# drive.net
KiCad netlist of a schematic drawn in Altium Designer
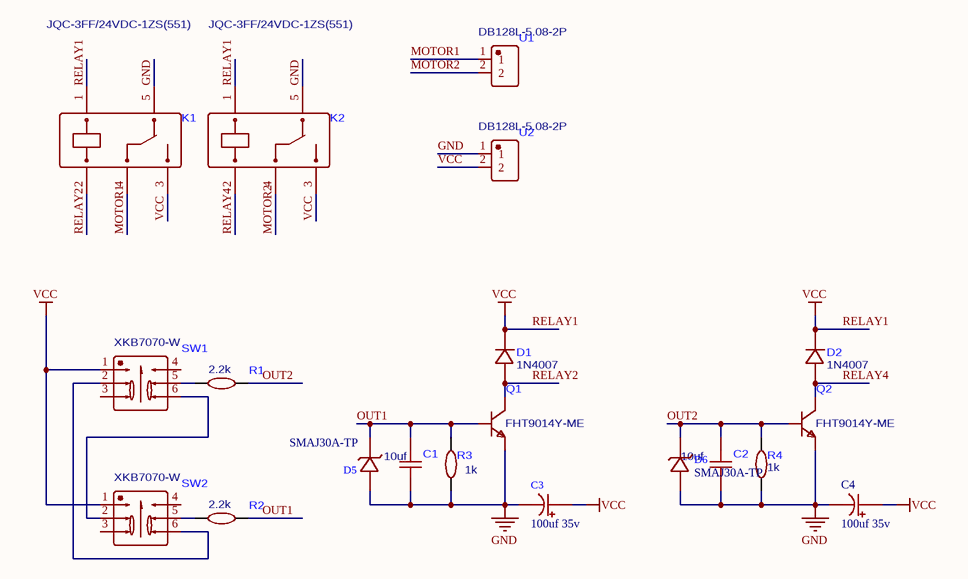
[diagram p0: drive.SchDoc]

(export (version "E")
  (design (tool "Eeschema 10.0.6"))
  (components
    (comp (ref "C1") (value "10uf") (footprint "C1210") (libsource (lib "test") (part "EMK325ABJ107MM-P")))
    (comp (ref "C2") (value "10uf") (footprint "C1210") (libsource (lib "test") (part "EMK325ABJ107MM-P")))
    (comp (ref "C3") (value "100uf 35v") (footprint "100uf 35v") (libsource (lib "test") (part "100uf 35v")))
    (comp (ref "C4") (value "100uf 35v") (footprint "100uf 35v") (libsource (lib "test") (part "100uf 35v")))
    (comp (ref "D1")
      (value "1N4007")
      (footprint "SMA_L4.4-W2.6-LS5.0-RD")
      (libsource (lib "test") (part "1N4007"))
    )
    (comp (ref "D2")
      (value "1N4007")
      (footprint "SMA_L4.4-W2.6-LS5.0-RD")
      (libsource (lib "test") (part "1N4007"))
    )
    (comp (ref "D5")
      (value "SMAJ30A-TP")
      (footprint "SMAJ16A-TP")
      (libsource (lib "test") (part "SMAJ16A-TP"))
    )
    (comp (ref "D6")
      (value "SMAJ30A-TP")
      (footprint "SMAJ16A-TP")
      (libsource (lib "test") (part "SMAJ16A-TP"))
    )
    (comp (ref "K1")
      (value "JQC-3FF/24VDC-1ZS(551)")
      (footprint "RELAY-TH_HF3FF/XX-1ZXX(XXX)")
      (libsource (lib "test") (part "JQC-3FF/12VDC-1ZS(551)"))
    )
    (comp (ref "K2")
      (value "JQC-3FF/24VDC-1ZS(551)")
      (footprint "RELAY-TH_HF3FF/XX-1ZXX(XXX)")
      (libsource (lib "test") (part "JQC-3FF/12VDC-1ZS(551)"))
    )
    (comp (ref "Q1")
      (value "FHT9014Y-ME")
      (footprint "SOT-23-3_L2.9-W1.3-P1.90-LS2.4-BR")
      (libsource (lib "test") (part "FHT9014Y-ME"))
    )
    (comp (ref "Q2")
      (value "FHT9014Y-ME")
      (footprint "SOT-23-3_L2.9-W1.3-P1.90-LS2.4-BR")
      (libsource (lib "test") (part "FHT9014Y-ME"))
    )
    (comp (ref "R1") (value "2.2k") (footprint "R0402") (libsource (lib "test") (part "MFR0S2F1001A20")))
    (comp (ref "R2") (value "2.2k") (footprint "R0402") (libsource (lib "test") (part "MFR0S2F1001A20")))
    (comp (ref "R3") (value "1k") (footprint "R0402") (libsource (lib "test") (part "MFR0S2F1001A20")))
    (comp (ref "R4") (value "1k") (footprint "R0402") (libsource (lib "test") (part "MFR0S2F1001A20")))
    (comp (ref "SW1")
      (value "XKB7070-W")
      (footprint "SW-TH_6P-L7.2-W7.2-P2.00-LS5.0")
      (libsource (lib "test") (part "XKB7070-W"))
    )
    (comp (ref "SW2")
      (value "XKB7070-W")
      (footprint "SW-TH_6P-L7.2-W7.2-P2.00-LS5.0")
      (libsource (lib "test") (part "XKB7070-W"))
    )
    (comp (ref "U1")
      (value "DB128L-5.08-2P")
      (footprint "CONN-TH_2P-P5.08_DB128L-5.08-2P")
      (libsource (lib "test") (part "DB128L-5.08-2P"))
    )
    (comp (ref "U2")
      (value "DB128L-5.08-2P")
      (footprint "CONN-TH_2P-P5.08_DB128L-5.08-2P")
      (libsource (lib "test") (part "DB128L-5.08-2P"))
    )
  )
  (nets
    (net (code "1") (name "/MOTOR1") (class "Default")
      (node (ref "K1") (pin "4") (pinfunction "4_4") (pintype "passive"))
      (node (ref "U1") (pin "1") (pinfunction "1_1") (pintype "passive"))
    )
    (net (code "2") (name "/MOTOR2") (class "Default")
      (node (ref "K2") (pin "4") (pinfunction "4_4") (pintype "passive"))
      (node (ref "U1") (pin "2") (pinfunction "2_2") (pintype "passive"))
    )
    (net (code "3") (name "/OUT1") (class "Default")
      (node (ref "C1") (pin "1") (pinfunction "1_1") (pintype "passive"))
      (node (ref "D5") (pin "1") (pinfunction "K_1") (pintype "passive"))
      (node (ref "Q1") (pin "1") (pinfunction "B_1") (pintype "passive"))
      (node (ref "R2") (pin "2") (pinfunction "2_2") (pintype "passive"))
      (node (ref "R3") (pin "2") (pinfunction "2_2") (pintype "passive"))
    )
    (net (code "4") (name "/OUT2") (class "Default")
      (node (ref "C2") (pin "1") (pinfunction "1_1") (pintype "passive"))
      (node (ref "D6") (pin "1") (pinfunction "K_1") (pintype "passive"))
      (node (ref "Q2") (pin "1") (pinfunction "B_1") (pintype "passive"))
      (node (ref "R1") (pin "2") (pinfunction "2_2") (pintype "passive"))
      (node (ref "R4") (pin "2") (pinfunction "2_2") (pintype "passive"))
    )
    (net (code "5") (name "/RELAY2") (class "Default")
      (node (ref "D1") (pin "2") (pinfunction "A_2") (pintype "passive"))
      (node (ref "K1") (pin "2") (pinfunction "2_2") (pintype "passive"))
      (node (ref "Q1") (pin "3") (pinfunction "C_3") (pintype "passive"))
    )
    (net (code "6") (name "/RELAY4") (class "Default")
      (node (ref "D2") (pin "2") (pinfunction "A_2") (pintype "passive"))
      (node (ref "K2") (pin "2") (pinfunction "2_2") (pintype "passive"))
      (node (ref "Q2") (pin "3") (pinfunction "C_3") (pintype "passive"))
    )
    (net (code "7") (name "GND") (class "Default")
      (node (ref "C1") (pin "2") (pinfunction "2_2") (pintype "passive"))
      (node (ref "C2") (pin "2") (pinfunction "2_2") (pintype "passive"))
      (node (ref "C3") (pin "2") (pinfunction "2_2") (pintype "passive"))
      (node (ref "C4") (pin "2") (pinfunction "2_2") (pintype "passive"))
      (node (ref "D5") (pin "2") (pinfunction "A_2") (pintype "passive"))
      (node (ref "D6") (pin "2") (pinfunction "A_2") (pintype "passive"))
      (node (ref "K1") (pin "5") (pinfunction "5_5") (pintype "passive"))
      (node (ref "K2") (pin "5") (pinfunction "5_5") (pintype "passive"))
      (node (ref "Q1") (pin "2") (pinfunction "E_2") (pintype "passive"))
      (node (ref "Q2") (pin "2") (pinfunction "E_2") (pintype "passive"))
      (node (ref "R3") (pin "1") (pinfunction "1_1") (pintype "passive"))
      (node (ref "R4") (pin "1") (pinfunction "1_1") (pintype "passive"))
      (node (ref "U2") (pin "1") (pinfunction "1_1") (pintype "passive"))
    )
    (net (code "8") (name "Net-(R1-Pad1)") (class "Default")
      (node (ref "R1") (pin "1") (pinfunction "1_1") (pintype "passive"))
      (node (ref "SW1") (pin "5") (pinfunction "5_5") (pintype "passive"))
    )
    (net (code "9") (name "Net-(R2-Pad1)") (class "Default")
      (node (ref "R2") (pin "1") (pinfunction "1_1") (pintype "passive"))
      (node (ref "SW2") (pin "5") (pinfunction "5_5") (pintype "passive"))
    )
    (net (code "10") (name "Net-(SW1-Pad2)") (class "Default")
      (node (ref "SW1") (pin "2") (pinfunction "2_2") (pintype "passive"))
      (node (ref "SW2") (pin "6") (pinfunction "6_6") (pintype "passive"))
    )
    (net (code "11") (name "Net-(SW1-Pad6)") (class "Default")
      (node (ref "SW1") (pin "6") (pinfunction "6_6") (pintype "passive"))
      (node (ref "SW2") (pin "2") (pinfunction "2_2") (pintype "passive"))
    )
    (net (code "12") (name "VCC") (class "Default")
      (node (ref "C3") (pin "1") (pinfunction "1_1") (pintype "passive"))
      (node (ref "C4") (pin "1") (pinfunction "1_1") (pintype "passive"))
      (node (ref "D1") (pin "1") (pinfunction "K_1") (pintype "passive"))
      (node (ref "D2") (pin "1") (pinfunction "K_1") (pintype "passive"))
      (node (ref "K1") (pin "1") (pinfunction "1_1") (pintype "passive"))
      (node (ref "K1") (pin "3") (pinfunction "3_3") (pintype "passive"))
      (node (ref "K2") (pin "1") (pinfunction "1_1") (pintype "passive"))
      (node (ref "K2") (pin "3") (pinfunction "3_3") (pintype "passive"))
      (node (ref "SW1") (pin "1") (pinfunction "1_1") (pintype "passive"))
      (node (ref "SW2") (pin "1") (pinfunction "1_1") (pintype "passive"))
      (node (ref "U2") (pin "2") (pinfunction "2_2") (pintype "passive"))
    )
    (net (code "13") (name "unconnected-(SW1-Pad3)") (class "Default")
      (node (ref "SW1") (pin "3") (pinfunction "3_3") (pintype "passive"))
    )
    (net (code "14") (name "unconnected-(SW1-Pad4)") (class "Default")
      (node (ref "SW1") (pin "4") (pinfunction "4_4") (pintype "passive"))
    )
    (net (code "15") (name "unconnected-(SW2-Pad3)") (class "Default")
      (node (ref "SW2") (pin "3") (pinfunction "3_3") (pintype "passive"))
    )
    (net (code "16") (name "unconnected-(SW2-Pad4)") (class "Default")
      (node (ref "SW2") (pin "4") (pinfunction "4_4") (pintype "passive"))
    )
  )
)
